# NguyenLy.net
KiCad netlist of a schematic drawn in Altium Designer
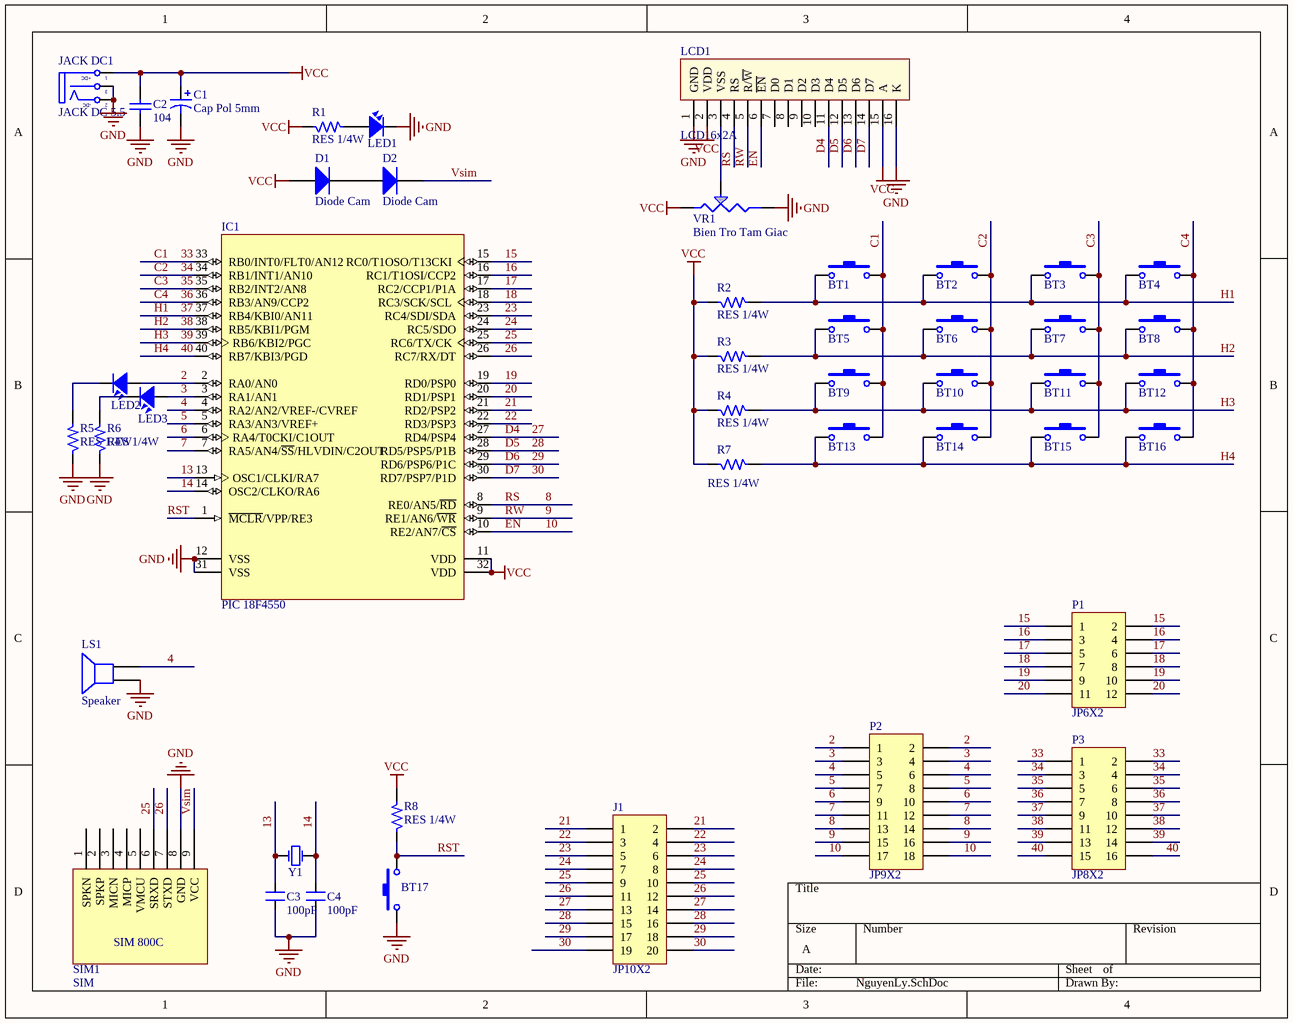
[diagram p0: NguyenLy.SchDoc]

(export (version "E")
  (design (tool "Eeschema 10.0.6"))
  (components
    (comp (ref "BT1")
      (value "Nut Nhan 2 Chan")
      (footprint "Nut Nhan 2 Chan")
      (fields (field (name "PUBLISHER") "Altium Limited"))
      (libsource (lib "LinhKienMCU.com") (part "Nut Nhan 2 Chan"))
    )
    (comp (ref "BT2")
      (value "Nut Nhan 2 Chan")
      (footprint "Nut Nhan 2 Chan")
      (fields (field (name "PUBLISHER") "Altium Limited"))
      (libsource (lib "LinhKienMCU.com") (part "Nut Nhan 2 Chan"))
    )
    (comp (ref "BT3")
      (value "Nut Nhan 2 Chan")
      (footprint "Nut Nhan 2 Chan")
      (fields (field (name "PUBLISHER") "Altium Limited"))
      (libsource (lib "LinhKienMCU.com") (part "Nut Nhan 2 Chan"))
    )
    (comp (ref "BT4")
      (value "Nut Nhan 2 Chan")
      (footprint "Nut Nhan 2 Chan")
      (fields (field (name "PUBLISHER") "Altium Limited"))
      (libsource (lib "LinhKienMCU.com") (part "Nut Nhan 2 Chan"))
    )
    (comp (ref "BT5")
      (value "Nut Nhan 2 Chan")
      (footprint "Nut Nhan 2 Chan")
      (fields (field (name "PUBLISHER") "Altium Limited"))
      (libsource (lib "LinhKienMCU.com") (part "Nut Nhan 2 Chan"))
    )
    (comp (ref "BT6")
      (value "Nut Nhan 2 Chan")
      (footprint "Nut Nhan 2 Chan")
      (fields (field (name "PUBLISHER") "Altium Limited"))
      (libsource (lib "LinhKienMCU.com") (part "Nut Nhan 2 Chan"))
    )
    (comp (ref "BT7")
      (value "Nut Nhan 2 Chan")
      (footprint "Nut Nhan 2 Chan")
      (fields (field (name "PUBLISHER") "Altium Limited"))
      (libsource (lib "LinhKienMCU.com") (part "Nut Nhan 2 Chan"))
    )
    (comp (ref "BT8")
      (value "Nut Nhan 2 Chan")
      (footprint "Nut Nhan 2 Chan")
      (fields (field (name "PUBLISHER") "Altium Limited"))
      (libsource (lib "LinhKienMCU.com") (part "Nut Nhan 2 Chan"))
    )
    (comp (ref "BT9")
      (value "Nut Nhan 2 Chan")
      (footprint "Nut Nhan 2 Chan")
      (fields (field (name "PUBLISHER") "Altium Limited"))
      (libsource (lib "LinhKienMCU.com") (part "Nut Nhan 2 Chan"))
    )
    (comp (ref "BT10")
      (value "Nut Nhan 2 Chan")
      (footprint "Nut Nhan 2 Chan")
      (fields (field (name "PUBLISHER") "Altium Limited"))
      (libsource (lib "LinhKienMCU.com") (part "Nut Nhan 2 Chan"))
    )
    (comp (ref "BT11")
      (value "Nut Nhan 2 Chan")
      (footprint "Nut Nhan 2 Chan")
      (fields (field (name "PUBLISHER") "Altium Limited"))
      (libsource (lib "LinhKienMCU.com") (part "Nut Nhan 2 Chan"))
    )
    (comp (ref "BT12")
      (value "Nut Nhan 2 Chan")
      (footprint "Nut Nhan 2 Chan")
      (fields (field (name "PUBLISHER") "Altium Limited"))
      (libsource (lib "LinhKienMCU.com") (part "Nut Nhan 2 Chan"))
    )
    (comp (ref "BT13")
      (value "Nut Nhan 2 Chan")
      (footprint "Nut Nhan 2 Chan")
      (fields (field (name "PUBLISHER") "Altium Limited"))
      (libsource (lib "LinhKienMCU.com") (part "Nut Nhan 2 Chan"))
    )
    (comp (ref "BT14")
      (value "Nut Nhan 2 Chan")
      (footprint "Nut Nhan 2 Chan")
      (fields (field (name "PUBLISHER") "Altium Limited"))
      (libsource (lib "LinhKienMCU.com") (part "Nut Nhan 2 Chan"))
    )
    (comp (ref "BT15")
      (value "Nut Nhan 2 Chan")
      (footprint "Nut Nhan 2 Chan")
      (fields (field (name "PUBLISHER") "Altium Limited"))
      (libsource (lib "LinhKienMCU.com") (part "Nut Nhan 2 Chan"))
    )
    (comp (ref "BT16")
      (value "Nut Nhan 2 Chan")
      (footprint "Nut Nhan 2 Chan")
      (fields (field (name "PUBLISHER") "Altium Limited"))
      (libsource (lib "LinhKienMCU.com") (part "Nut Nhan 2 Chan"))
    )
    (comp (ref "BT17")
      (value "Nut Nhan 2 Chan")
      (footprint "Nut Nhan 2 Chan")
      (fields (field (name "PUBLISHER") "Altium Limited"))
      (libsource (lib "LinhKienMCU.com") (part "Nut Nhan 2 Chan"))
    )
    (comp (ref "C1")
      (value "Cap Pol 5mm")
      (footprint "C5mm")
      (description "Polarized Capacitor (Axial)")
      (fields (field (name "PUBLISHER") "Altium Limited"))
      (libsource (lib "LinhKienMCU.com") (part "Cap Pol 5mm"))
    )
    (comp (ref "C2")
      (value "104")
      (footprint "Tu-ceramic")
      (libsource (lib "LinhKienMCU.com") (part "CAP 104-TANTALUM"))
    )
    (comp (ref "C3")
      (value "100pF")
      (footprint "CN1")
      (description "Cap np  1pF - 472pF")
      (libsource (lib "Cty1") (part "CN1"))
    )
    (comp (ref "C4")
      (value "100pF")
      (footprint "CN1")
      (description "Cap np  1pF - 472pF")
      (libsource (lib "Cty1") (part "CN1"))
    )
    (comp (ref "D1")
      (value "Diode Cam")
      (footprint "Diode Cam")
      (fields (field (name "PUBLISHER") "Altium Limited"))
      (libsource (lib "LinhKienMCU.com") (part "Diode Cam"))
    )
    (comp (ref "D2")
      (value "Diode Cam")
      (footprint "Diode Cam")
      (fields (field (name "PUBLISHER") "Altium Limited"))
      (libsource (lib "LinhKienMCU.com") (part "Diode Cam"))
    )
    (comp (ref "IC1")
      (value "PIC 18F4550")
      (footprint "DIP40/W0.6")
      (description "32KB Flash, 1536B RAM, 256B EFROM, 40-Pin PDIP")
      (fields (field (name "COPYRIGHT BY") "VanDungEvn"))
      (libsource (lib "Cty1") (part "PIC 18F4520"))
    )
    (comp (ref "J1")
      (value "JP10X2")
      (footprint "HDR2X10")
      (description "JUMP DOI DUC THANG")
      (fields (field (name "PUBLISHER") "Altium Limited"))
      (libsource (lib "LinhKienMCU.com") (part "JUMP DOI-10P"))
    )
    (comp (ref "JACK DC1")
      (value "JACK DC 5.5")
      (footprint "JACK DC 5.5")
      (libsource (lib "LinhKienMCU.com") (part "JACK DC 5.5"))
    )
    (comp (ref "LCD1")
      (value "LCD16x2A")
      (footprint "LCD16X2")
      (description "JUMP DON CAI")
      (libsource (lib "LinhKienMCU.com") (part "LCD16X2"))
    )
    (comp (ref "LED1")
      (value "LED")
      (footprint "LED-3MM-YELLOW")
      (description "LED Single colour Green and Red")
      (libsource (lib "LIBRARY") (part "LED"))
    )
    (comp (ref "LED2")
      (value "LED")
      (footprint "LED-3MM-YELLOW")
      (description "LED Single colour Green and Red")
      (libsource (lib "LIBRARY") (part "LED"))
    )
    (comp (ref "LED3")
      (value "LED")
      (footprint "LED-3MM-YELLOW")
      (description "LED Single colour Green and Red")
      (libsource (lib "LIBRARY") (part "LED"))
    )
    (comp (ref "LS1")
      (value "Speaker")
      (footprint "SPK")
      (description "Loudspeaker")
      (fields (field (name "PUBLISHER") "Altium Limited"))
      (libsource (lib "LinhKienMCU.com") (part "Speaker"))
    )
    (comp (ref "P1")
      (value "JP6X2")
      (footprint "HDR2X6")
      (description "JUMP DOI DUC THANG")
      (fields (field (name "PUBLISHER") "Altium Limited"))
      (libsource (lib "LinhKienMCU.com") (part "JUMP DOI-6"))
    )
    (comp (ref "P2")
      (value "JP9X2")
      (footprint "HDR2X9")
      (description "JUMP DOI DUC THANG")
      (fields (field (name "PUBLISHER") "Altium Limited"))
      (libsource (lib "LinhKienMCU.com") (part "JUMP DOI-9P"))
    )
    (comp (ref "P3")
      (value "JP8X2")
      (footprint "HDR2X8")
      (description "JUMP DOI DUC THANG")
      (fields (field (name "PUBLISHER") "Altium Limited"))
      (libsource (lib "LinhKienMCU.com") (part "JUMP DOI-8P"))
    )
    (comp (ref "R1")
      (value "RES 1/4W")
      (footprint "Tro 1/4W")
      (description "Tro 1/4W")
      (libsource (lib "LinhKienMCU.com") (part "RES 1/4W"))
    )
    (comp (ref "R2")
      (value "RES 1/4W")
      (footprint "Tro 1/4W")
      (description "Tro 1/4W")
      (libsource (lib "LinhKienMCU.com") (part "RES 1/4W"))
    )
    (comp (ref "R3")
      (value "RES 1/4W")
      (footprint "Tro 1/4W")
      (description "Tro 1/4W")
      (libsource (lib "LinhKienMCU.com") (part "RES 1/4W"))
    )
    (comp (ref "R4")
      (value "RES 1/4W")
      (footprint "Tro 1/4W")
      (description "Tro 1/4W")
      (libsource (lib "LinhKienMCU.com") (part "RES 1/4W"))
    )
    (comp (ref "R5")
      (value "RES 1/4W")
      (footprint "Tro 1/4W")
      (description "Tro 1/4W")
      (libsource (lib "LinhKienMCU.com") (part "RES 1/4W"))
    )
    (comp (ref "R6")
      (value "RES 1/4W")
      (footprint "Tro 1/4W")
      (description "Tro 1/4W")
      (libsource (lib "LinhKienMCU.com") (part "RES 1/4W"))
    )
    (comp (ref "R7")
      (value "RES 1/4W")
      (footprint "Tro 1/4W")
      (description "Tro 1/4W")
      (libsource (lib "LinhKienMCU.com") (part "RES 1/4W"))
    )
    (comp (ref "R8")
      (value "RES 1/4W")
      (footprint "Tro 1/4W")
      (description "Tro 1/4W")
      (libsource (lib "LinhKienMCU.com") (part "RES 1/4W"))
    )
    (comp (ref "SIM1") (value "SIM") (footprint "JUMP DON 9") (libsource (lib "Schlib1") (part "SIM800C")))
    (comp (ref "VR1")
      (value "Bien Tro Tam Giac")
      (footprint "VR-TAM GIAC")
      (libsource (lib "LinhKienMCU.com") (part "Bien Tro Tam Giac"))
    )
    (comp (ref "Y1")
      (value "20MHz")
      (footprint "Thach anh 2 chan")
      (description "Thach Anh Cam")
      (fields (field (name "PUBLISHER") "Altium Limited"))
      (libsource (lib "LinhKienMCU.com") (part "Thach Anh Cam"))
    )
  )
  (nets
    (net (code "1") (name "/2") (class "Default")
      (node (ref "IC1") (pin "2") (pinfunction "RA0/AN0_2") (pintype "bidirectional"))
      (node (ref "LED2") (pin "1") (pinfunction "1_1") (pintype "passive"))
      (node (ref "P2") (pin "1") (pinfunction "1_1") (pintype "passive"))
      (node (ref "P2") (pin "2") (pinfunction "2_2") (pintype "passive"))
    )
    (net (code "2") (name "/3") (class "Default")
      (node (ref "IC1") (pin "3") (pinfunction "RA1/AN1_3") (pintype "bidirectional"))
      (node (ref "LED3") (pin "1") (pinfunction "1_1") (pintype "passive"))
      (node (ref "P2") (pin "3") (pinfunction "3_3") (pintype "passive"))
      (node (ref "P2") (pin "4") (pinfunction "4_4") (pintype "passive"))
    )
    (net (code "3") (name "/4") (class "Default")
      (node (ref "IC1") (pin "4") (pinfunction "RA2/AN2/VREF-/CVREF_4") (pintype "bidirectional"))
      (node (ref "LS1") (pin "2") (pinfunction "2_2") (pintype "passive"))
      (node (ref "P2") (pin "5") (pinfunction "5_5") (pintype "passive"))
      (node (ref "P2") (pin "6") (pinfunction "6_6") (pintype "passive"))
    )
    (net (code "4") (name "/5") (class "Default")
      (node (ref "IC1") (pin "5") (pinfunction "RA3/AN3/VREF+_5") (pintype "bidirectional"))
      (node (ref "P2") (pin "7") (pinfunction "7_7") (pintype "passive"))
      (node (ref "P2") (pin "8") (pinfunction "8_8") (pintype "passive"))
    )
    (net (code "5") (name "/6") (class "Default")
      (node (ref "IC1") (pin "6") (pinfunction "RA4/T0CKI/C1OUT_6") (pintype "bidirectional"))
      (node (ref "P2") (pin "10") (pinfunction "10_10") (pintype "passive"))
      (node (ref "P2") (pin "9") (pinfunction "9_9") (pintype "passive"))
    )
    (net (code "6") (name "/7") (class "Default")
      (node (ref "IC1") (pin "7") (pinfunction "RA5/AN4/~{SS}/HLVDIN/C2OUT_7") (pintype "bidirectional"))
      (node (ref "P2") (pin "11") (pinfunction "11_11") (pintype "passive"))
      (node (ref "P2") (pin "12") (pinfunction "12_12") (pintype "passive"))
    )
    (net (code "7") (name "/8") (class "Default")
      (node (ref "IC1") (pin "8") (pinfunction "RE0/AN5/~{RD}_8") (pintype "bidirectional"))
      (node (ref "LCD1") (pin "4") (pinfunction "RS_4") (pintype "passive"))
      (node (ref "P2") (pin "13") (pinfunction "13_13") (pintype "passive"))
      (node (ref "P2") (pin "14") (pinfunction "14_14") (pintype "passive"))
    )
    (net (code "8") (name "/9") (class "Default")
      (node (ref "IC1") (pin "9") (pinfunction "RE1/AN6/~{WR}_9") (pintype "bidirectional"))
      (node (ref "LCD1") (pin "5") (pinfunction "R/~{W}_5") (pintype "passive"))
      (node (ref "P2") (pin "15") (pinfunction "15_15") (pintype "passive"))
      (node (ref "P2") (pin "16") (pinfunction "16_16") (pintype "passive"))
    )
    (net (code "9") (name "/10") (class "Default")
      (node (ref "IC1") (pin "10") (pinfunction "RE2/AN7/~{CS}_10") (pintype "bidirectional"))
      (node (ref "LCD1") (pin "6") (pinfunction "~{EN}_6") (pintype "passive"))
      (node (ref "P2") (pin "17") (pinfunction "17_17") (pintype "passive"))
      (node (ref "P2") (pin "18") (pinfunction "18_18") (pintype "passive"))
    )
    (net (code "10") (name "/13") (class "Default")
      (node (ref "C3") (pin "1") (pinfunction "1_1") (pintype "passive"))
      (node (ref "IC1") (pin "13") (pinfunction "OSC1/CLKI/RA7_13") (pintype "input"))
      (node (ref "Y1") (pin "2") (pinfunction "OSC2_2") (pintype "passive"))
    )
    (net (code "11") (name "/14") (class "Default")
      (node (ref "C4") (pin "1") (pinfunction "1_1") (pintype "passive"))
      (node (ref "IC1") (pin "14") (pinfunction "OSC2/CLKO/RA6_14") (pintype "bidirectional"))
      (node (ref "Y1") (pin "1") (pinfunction "OSC1_1") (pintype "passive"))
    )
    (net (code "12") (name "/15") (class "Default")
      (node (ref "IC1") (pin "15") (pinfunction "RC0/T1OSO/T13CKI_15") (pintype "bidirectional"))
      (node (ref "P1") (pin "1") (pinfunction "1_1") (pintype "passive"))
      (node (ref "P1") (pin "2") (pinfunction "2_2") (pintype "passive"))
    )
    (net (code "13") (name "/16") (class "Default")
      (node (ref "IC1") (pin "16") (pinfunction "RC1/T1OSI/CCP2_16") (pintype "bidirectional"))
      (node (ref "P1") (pin "3") (pinfunction "3_3") (pintype "passive"))
      (node (ref "P1") (pin "4") (pinfunction "4_4") (pintype "passive"))
    )
    (net (code "14") (name "/17") (class "Default")
      (node (ref "IC1") (pin "17") (pinfunction "RC2/CCP1/P1A_17") (pintype "bidirectional"))
      (node (ref "P1") (pin "5") (pinfunction "5_5") (pintype "passive"))
      (node (ref "P1") (pin "6") (pinfunction "6_6") (pintype "passive"))
    )
    (net (code "15") (name "/18") (class "Default")
      (node (ref "IC1") (pin "18") (pinfunction "RC3/SCK/SCL_18") (pintype "bidirectional"))
      (node (ref "P1") (pin "7") (pinfunction "7_7") (pintype "passive"))
      (node (ref "P1") (pin "8") (pinfunction "8_8") (pintype "passive"))
    )
    (net (code "16") (name "/19") (class "Default")
      (node (ref "IC1") (pin "19") (pinfunction "RD0/PSP0_19") (pintype "bidirectional"))
      (node (ref "P1") (pin "10") (pinfunction "10_10") (pintype "passive"))
      (node (ref "P1") (pin "9") (pinfunction "9_9") (pintype "passive"))
    )
    (net (code "17") (name "/20") (class "Default")
      (node (ref "IC1") (pin "20") (pinfunction "RD1/PSP1_20") (pintype "bidirectional"))
      (node (ref "P1") (pin "11") (pinfunction "11_11") (pintype "passive"))
      (node (ref "P1") (pin "12") (pinfunction "12_12") (pintype "passive"))
    )
    (net (code "18") (name "/21") (class "Default")
      (node (ref "IC1") (pin "21") (pinfunction "RD2/PSP2_21") (pintype "bidirectional"))
      (node (ref "J1") (pin "1") (pinfunction "1_1") (pintype "passive"))
      (node (ref "J1") (pin "2") (pinfunction "2_2") (pintype "passive"))
    )
    (net (code "19") (name "/22") (class "Default")
      (node (ref "IC1") (pin "22") (pinfunction "RD3/PSP3_22") (pintype "bidirectional"))
      (node (ref "J1") (pin "3") (pinfunction "3_3") (pintype "passive"))
      (node (ref "J1") (pin "4") (pinfunction "4_4") (pintype "passive"))
    )
    (net (code "20") (name "/23") (class "Default")
      (node (ref "IC1") (pin "23") (pinfunction "RC4/SDI/SDA_23") (pintype "bidirectional"))
      (node (ref "J1") (pin "5") (pinfunction "5_5") (pintype "passive"))
      (node (ref "J1") (pin "6") (pinfunction "6_6") (pintype "passive"))
    )
    (net (code "21") (name "/24") (class "Default")
      (node (ref "IC1") (pin "24") (pinfunction "RC5/SDO_24") (pintype "bidirectional"))
      (node (ref "J1") (pin "7") (pinfunction "7_7") (pintype "passive"))
      (node (ref "J1") (pin "8") (pinfunction "8_8") (pintype "passive"))
    )
    (net (code "22") (name "/25") (class "Default")
      (node (ref "IC1") (pin "25") (pinfunction "RC6/TX/CK_25") (pintype "bidirectional"))
      (node (ref "J1") (pin "10") (pinfunction "10_10") (pintype "passive"))
      (node (ref "J1") (pin "9") (pinfunction "9_9") (pintype "passive"))
      (node (ref "SIM1") (pin "6") (pinfunction "SRXD_6") (pintype "passive"))
    )
    (net (code "23") (name "/26") (class "Default")
      (node (ref "IC1") (pin "26") (pinfunction "RC7/RX/DT_26") (pintype "bidirectional"))
      (node (ref "J1") (pin "11") (pinfunction "11_11") (pintype "passive"))
      (node (ref "J1") (pin "12") (pinfunction "12_12") (pintype "passive"))
      (node (ref "SIM1") (pin "7") (pinfunction "STXD_7") (pintype "passive"))
    )
    (net (code "24") (name "/27") (class "Default")
      (node (ref "IC1") (pin "27") (pinfunction "RD4/PSP4_27") (pintype "bidirectional"))
      (node (ref "J1") (pin "13") (pinfunction "13_13") (pintype "passive"))
      (node (ref "J1") (pin "14") (pinfunction "14_14") (pintype "passive"))
      (node (ref "LCD1") (pin "11") (pinfunction "D4_11") (pintype "passive"))
    )
    (net (code "25") (name "/28") (class "Default")
      (node (ref "IC1") (pin "28") (pinfunction "RD5/PSP5/P1B_28") (pintype "bidirectional"))
      (node (ref "J1") (pin "15") (pinfunction "15_15") (pintype "passive"))
      (node (ref "J1") (pin "16") (pinfunction "16_16") (pintype "passive"))
      (node (ref "LCD1") (pin "12") (pinfunction "D5_12") (pintype "passive"))
    )
    (net (code "26") (name "/29") (class "Default")
      (node (ref "IC1") (pin "29") (pinfunction "RD6/PSP6/P1C_29") (pintype "bidirectional"))
      (node (ref "J1") (pin "17") (pinfunction "17_17") (pintype "passive"))
      (node (ref "J1") (pin "18") (pinfunction "18_18") (pintype "passive"))
      (node (ref "LCD1") (pin "13") (pinfunction "D6_13") (pintype "passive"))
    )
    (net (code "27") (name "/30") (class "Default")
      (node (ref "IC1") (pin "30") (pinfunction "RD7/PSP7/P1D_30") (pintype "bidirectional"))
      (node (ref "J1") (pin "19") (pinfunction "19_19") (pintype "passive"))
      (node (ref "J1") (pin "20") (pinfunction "20_20") (pintype "passive"))
      (node (ref "LCD1") (pin "14") (pinfunction "D7_14") (pintype "passive"))
    )
    (net (code "28") (name "/33") (class "Default")
      (node (ref "BT1") (pin "2") (pinfunction "2_2") (pintype "passive"))
      (node (ref "BT13") (pin "2") (pinfunction "2_2") (pintype "passive"))
      (node (ref "BT5") (pin "2") (pinfunction "2_2") (pintype "passive"))
      (node (ref "BT9") (pin "2") (pinfunction "2_2") (pintype "passive"))
      (node (ref "IC1") (pin "33") (pinfunction "RB0/INT0/FLT0/AN12_33") (pintype "bidirectional"))
      (node (ref "P3") (pin "1") (pinfunction "1_1") (pintype "passive"))
      (node (ref "P3") (pin "2") (pinfunction "2_2") (pintype "passive"))
    )
    (net (code "29") (name "/34") (class "Default")
      (node (ref "BT10") (pin "2") (pinfunction "2_2") (pintype "passive"))
      (node (ref "BT14") (pin "2") (pinfunction "2_2") (pintype "passive"))
      (node (ref "BT2") (pin "2") (pinfunction "2_2") (pintype "passive"))
      (node (ref "BT6") (pin "2") (pinfunction "2_2") (pintype "passive"))
      (node (ref "IC1") (pin "34") (pinfunction "RB1/INT1/AN10_34") (pintype "bidirectional"))
      (node (ref "P3") (pin "3") (pinfunction "3_3") (pintype "passive"))
      (node (ref "P3") (pin "4") (pinfunction "4_4") (pintype "passive"))
    )
    (net (code "30") (name "/35") (class "Default")
      (node (ref "BT11") (pin "2") (pinfunction "2_2") (pintype "passive"))
      (node (ref "BT15") (pin "2") (pinfunction "2_2") (pintype "passive"))
      (node (ref "BT3") (pin "2") (pinfunction "2_2") (pintype "passive"))
      (node (ref "BT7") (pin "2") (pinfunction "2_2") (pintype "passive"))
      (node (ref "IC1") (pin "35") (pinfunction "RB2/INT2/AN8_35") (pintype "bidirectional"))
      (node (ref "P3") (pin "5") (pinfunction "5_5") (pintype "passive"))
      (node (ref "P3") (pin "6") (pinfunction "6_6") (pintype "passive"))
    )
    (net (code "31") (name "/36") (class "Default")
      (node (ref "BT12") (pin "2") (pinfunction "2_2") (pintype "passive"))
      (node (ref "BT16") (pin "2") (pinfunction "2_2") (pintype "passive"))
      (node (ref "BT4") (pin "2") (pinfunction "2_2") (pintype "passive"))
      (node (ref "BT8") (pin "2") (pinfunction "2_2") (pintype "passive"))
      (node (ref "IC1") (pin "36") (pinfunction "RB3/AN9/CCP2_36") (pintype "bidirectional"))
      (node (ref "P3") (pin "7") (pinfunction "7_7") (pintype "passive"))
      (node (ref "P3") (pin "8") (pinfunction "8_8") (pintype "passive"))
    )
    (net (code "32") (name "/37") (class "Default")
      (node (ref "BT1") (pin "1") (pinfunction "1_1") (pintype "passive"))
      (node (ref "BT2") (pin "1") (pinfunction "1_1") (pintype "passive"))
      (node (ref "BT3") (pin "1") (pinfunction "1_1") (pintype "passive"))
      (node (ref "BT4") (pin "1") (pinfunction "1_1") (pintype "passive"))
      (node (ref "IC1") (pin "37") (pinfunction "RB4/KBI0/AN11_37") (pintype "bidirectional"))
      (node (ref "P3") (pin "10") (pinfunction "10_10") (pintype "passive"))
      (node (ref "P3") (pin "9") (pinfunction "9_9") (pintype "passive"))
      (node (ref "R2") (pin "2") (pinfunction "2_2") (pintype "passive"))
    )
    (net (code "33") (name "/38") (class "Default")
      (node (ref "BT5") (pin "1") (pinfunction "1_1") (pintype "passive"))
      (node (ref "BT6") (pin "1") (pinfunction "1_1") (pintype "passive"))
      (node (ref "BT7") (pin "1") (pinfunction "1_1") (pintype "passive"))
      (node (ref "BT8") (pin "1") (pinfunction "1_1") (pintype "passive"))
      (node (ref "IC1") (pin "38") (pinfunction "RB5/KBI1/PGM_38") (pintype "bidirectional"))
      (node (ref "P3") (pin "11") (pinfunction "11_11") (pintype "passive"))
      (node (ref "P3") (pin "12") (pinfunction "12_12") (pintype "passive"))
      (node (ref "R3") (pin "2") (pinfunction "2_2") (pintype "passive"))
    )
    (net (code "34") (name "/39") (class "Default")
      (node (ref "BT10") (pin "1") (pinfunction "1_1") (pintype "passive"))
      (node (ref "BT11") (pin "1") (pinfunction "1_1") (pintype "passive"))
      (node (ref "BT12") (pin "1") (pinfunction "1_1") (pintype "passive"))
      (node (ref "BT9") (pin "1") (pinfunction "1_1") (pintype "passive"))
      (node (ref "IC1") (pin "39") (pinfunction "RB6/KBI2/PGC_39") (pintype "bidirectional"))
      (node (ref "P3") (pin "13") (pinfunction "13_13") (pintype "passive"))
      (node (ref "P3") (pin "14") (pinfunction "14_14") (pintype "passive"))
      (node (ref "R4") (pin "2") (pinfunction "2_2") (pintype "passive"))
    )
    (net (code "35") (name "/40") (class "Default")
      (node (ref "BT13") (pin "1") (pinfunction "1_1") (pintype "passive"))
      (node (ref "BT14") (pin "1") (pinfunction "1_1") (pintype "passive"))
      (node (ref "BT15") (pin "1") (pinfunction "1_1") (pintype "passive"))
      (node (ref "BT16") (pin "1") (pinfunction "1_1") (pintype "passive"))
      (node (ref "IC1") (pin "40") (pinfunction "RB7/KBI3/PGD_40") (pintype "bidirectional"))
      (node (ref "P3") (pin "15") (pinfunction "15_15") (pintype "passive"))
      (node (ref "P3") (pin "16") (pinfunction "16_16") (pintype "passive"))
      (node (ref "R7") (pin "2") (pinfunction "2_2") (pintype "passive"))
    )
    (net (code "36") (name "/RST") (class "Default")
      (node (ref "BT17") (pin "2") (pinfunction "2_2") (pintype "passive"))
      (node (ref "IC1") (pin "1") (pinfunction "~{MCLR}/VPP/RE3_1") (pintype "input"))
      (node (ref "R8") (pin "1") (pinfunction "1_1") (pintype "passive"))
    )
    (net (code "37") (name "/Vsim") (class "Default")
      (node (ref "D2") (pin "2") (pinfunction "K_2") (pintype "passive"))
      (node (ref "SIM1") (pin "9") (pinfunction "VCC_9") (pintype "passive"))
    )
    (net (code "38") (name "GND") (class "Default")
      (node (ref "BT17") (pin "1") (pinfunction "1_1") (pintype "passive"))
      (node (ref "C1") (pin "2") (pinfunction "2_2") (pintype "passive"))
      (node (ref "C2") (pin "1") (pinfunction "1_1") (pintype "passive"))
      (node (ref "C3") (pin "2") (pinfunction "2_2") (pintype "passive"))
      (node (ref "C4") (pin "2") (pinfunction "2_2") (pintype "passive"))
      (node (ref "IC1") (pin "12") (pinfunction "VSS_12") (pintype "power_in"))
      (node (ref "IC1") (pin "31") (pinfunction "VSS_31") (pintype "power_in"))
      (node (ref "JACK DC1") (pin "2") (pinfunction "TN_2") (pintype "passive"))
      (node (ref "JACK DC1") (pin "3") (pinfunction "S_3") (pintype "power_in"))
      (node (ref "LCD1") (pin "1") (pinfunction "GND_1") (pintype "passive"))
      (node (ref "LCD1") (pin "16") (pinfunction "K_16") (pintype "passive"))
      (node (ref "LED1") (pin "2") (pinfunction "2_2") (pintype "passive"))
      (node (ref "LS1") (pin "1") (pinfunction "1_1") (pintype "passive"))
      (node (ref "R5") (pin "1") (pinfunction "1_1") (pintype "passive"))
      (node (ref "R6") (pin "1") (pinfunction "1_1") (pintype "passive"))
      (node (ref "SIM1") (pin "8") (pinfunction "GND_8") (pintype "passive"))
      (node (ref "VR1") (pin "3") (pinfunction "B_3") (pintype "passive"))
    )
    (net (code "39") (name "Net-(D1-K)") (class "Default")
      (node (ref "D1") (pin "2") (pinfunction "K_2") (pintype "passive"))
      (node (ref "D2") (pin "1") (pinfunction "A_1") (pintype "passive"))
    )
    (net (code "40") (name "Net-(LCD1-VSS)") (class "Default")
      (node (ref "LCD1") (pin "3") (pinfunction "VSS_3") (pintype "passive"))
      (node (ref "VR1") (pin "2") (pinfunction "WIPER_2") (pintype "passive"))
    )
    (net (code "41") (name "Net-(LED1-Pad1)") (class "Default")
      (node (ref "LED1") (pin "1") (pinfunction "1_1") (pintype "passive"))
      (node (ref "R1") (pin "2") (pinfunction "2_2") (pintype "passive"))
    )
    (net (code "42") (name "Net-(LED2-Pad2)") (class "Default")
      (node (ref "LED2") (pin "2") (pinfunction "2_2") (pintype "passive"))
      (node (ref "R5") (pin "2") (pinfunction "2_2") (pintype "passive"))
    )
    (net (code "43") (name "Net-(LED3-Pad2)") (class "Default")
      (node (ref "LED3") (pin "2") (pinfunction "2_2") (pintype "passive"))
      (node (ref "R6") (pin "2") (pinfunction "2_2") (pintype "passive"))
    )
    (net (code "44") (name "VCC") (class "Default")
      (node (ref "C1") (pin "1") (pinfunction "1_1") (pintype "passive"))
      (node (ref "C2") (pin "2") (pinfunction "2_2") (pintype "passive"))
      (node (ref "D1") (pin "1") (pinfunction "A_1") (pintype "passive"))
      (node (ref "IC1") (pin "11") (pinfunction "VDD_11") (pintype "power_in"))
      (node (ref "IC1") (pin "32") (pinfunction "VDD_32") (pintype "power_in"))
      (node (ref "JACK DC1") (pin "1") (pinfunction "T_1") (pintype "passive"))
      (node (ref "LCD1") (pin "15") (pinfunction "A_15") (pintype "passive"))
      (node (ref "LCD1") (pin "2") (pinfunction "VDD_2") (pintype "passive"))
      (node (ref "R1") (pin "1") (pinfunction "1_1") (pintype "passive"))
      (node (ref "R2") (pin "1") (pinfunction "1_1") (pintype "passive"))
      (node (ref "R3") (pin "1") (pinfunction "1_1") (pintype "passive"))
      (node (ref "R4") (pin "1") (pinfunction "1_1") (pintype "passive"))
      (node (ref "R7") (pin "1") (pinfunction "1_1") (pintype "passive"))
      (node (ref "R8") (pin "2") (pinfunction "2_2") (pintype "passive"))
      (node (ref "VR1") (pin "1") (pinfunction "A_1") (pintype "passive"))
    )
    (net (code "45") (name "unconnected-(LCD1-D0-Pad7)") (class "Default")
      (node (ref "LCD1") (pin "7") (pinfunction "D0_7") (pintype "passive"))
    )
    (net (code "46") (name "unconnected-(LCD1-D1-Pad8)") (class "Default")
      (node (ref "LCD1") (pin "8") (pinfunction "D1_8") (pintype "passive"))
    )
    (net (code "47") (name "unconnected-(LCD1-D2-Pad9)") (class "Default")
      (node (ref "LCD1") (pin "9") (pinfunction "D2_9") (pintype "passive"))
    )
    (net (code "48") (name "unconnected-(LCD1-D3-Pad10)") (class "Default")
      (node (ref "LCD1") (pin "10") (pinfunction "D3_10") (pintype "passive"))
    )
    (net (code "49") (name "unconnected-(SIM1-MICN-Pad3)") (class "Default")
      (node (ref "SIM1") (pin "3") (pinfunction "MICN_3") (pintype "passive"))
    )
    (net (code "50") (name "unconnected-(SIM1-MICP-Pad4)") (class "Default")
      (node (ref "SIM1") (pin "4") (pinfunction "MICP_4") (pintype "passive"))
    )
    (net (code "51") (name "unconnected-(SIM1-SPKN-Pad1)") (class "Default")
      (node (ref "SIM1") (pin "1") (pinfunction "SPKN_1") (pintype "passive"))
    )
    (net (code "52") (name "unconnected-(SIM1-SPKP-Pad2)") (class "Default")
      (node (ref "SIM1") (pin "2") (pinfunction "SPKP_2") (pintype "passive"))
    )
    (net (code "53") (name "unconnected-(SIM1-VMCU-Pad5)") (class "Default")
      (node (ref "SIM1") (pin "5") (pinfunction "VMCU_5") (pintype "passive"))
    )
  )
)
